# PS3604LF.net
KiCad netlist of a schematic drawn in Altium Designer
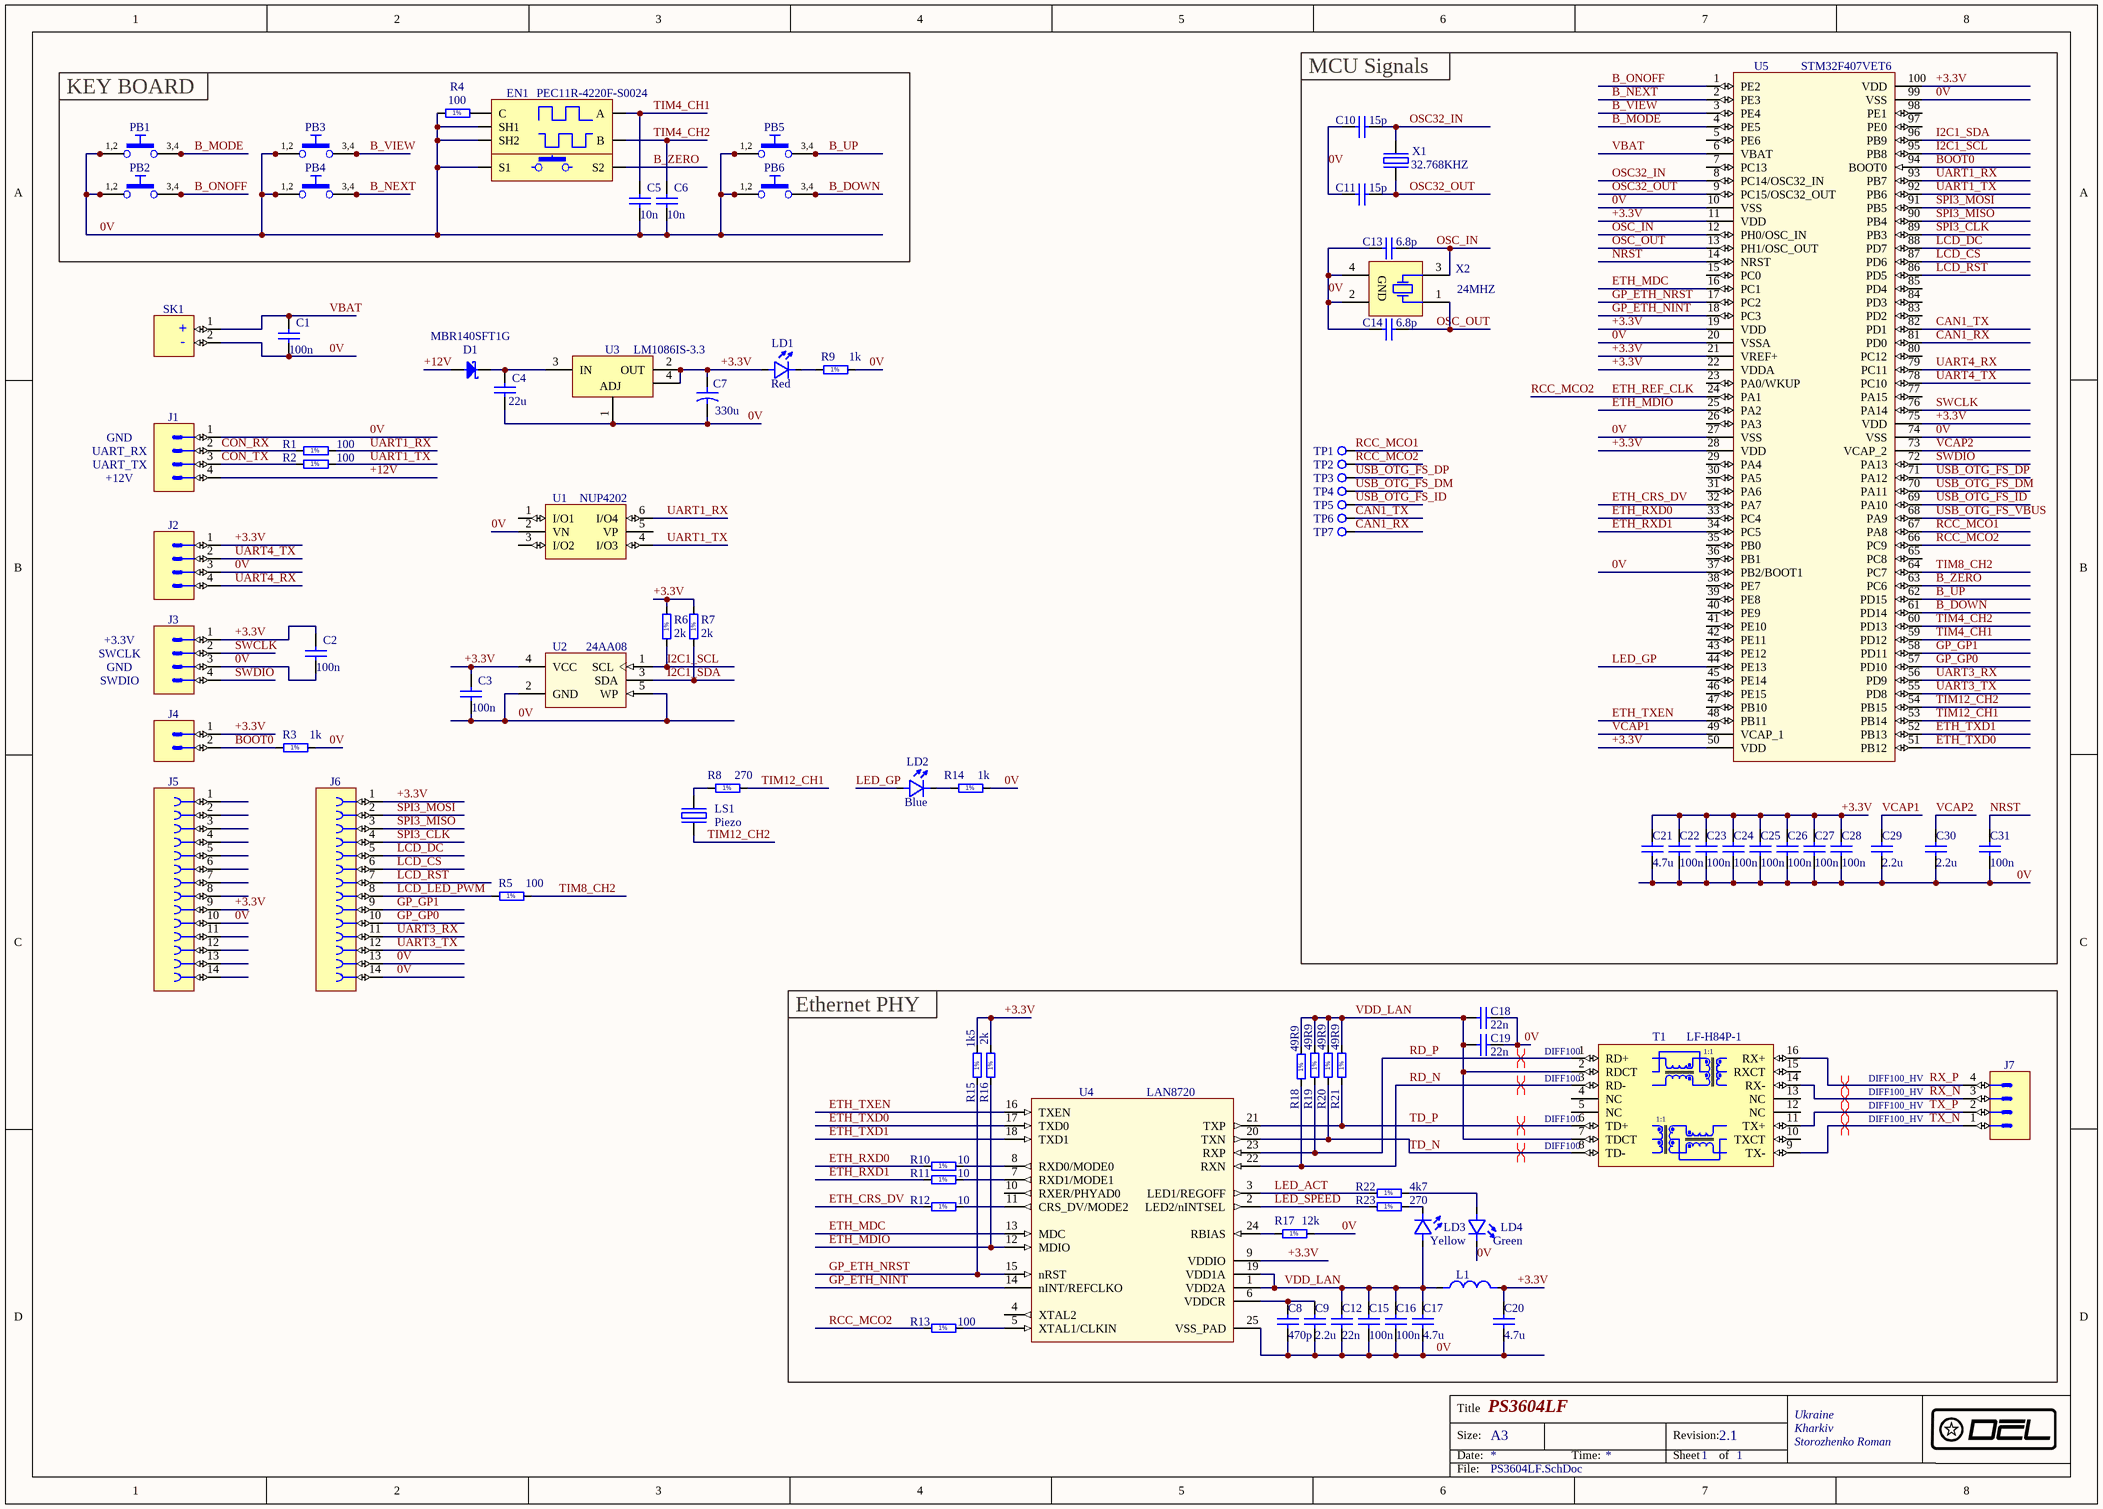
[diagram p0: PS3604LF.SchDoc]

(export (version "E")
  (design (tool "Eeschema 10.0.6"))
  (components
    (comp (ref "C1")
      (value "100n")
      (footprint "CAPC1005X55N")
      (description "Non-polarised capacitor")
      (fields
        (field (name "PART NUMBER") "CC0402_100NF_50V_10%_X7R")
        (field (name "VOLTAGE") "50V")
        (field (name "AUTHOR") "DEL")
      )
      (libsource (lib "Capacitors") (part "Capacitor - non polarized"))
    )
    (comp (ref "C2")
      (value "100n")
      (footprint "CAPC1005X55N")
      (description "Non-polarised capacitor")
      (fields
        (field (name "PART NUMBER") "CC0402_100NF_50V_10%_X7R")
        (field (name "VOLTAGE") "50V")
        (field (name "AUTHOR") "DEL")
      )
      (libsource (lib "Capacitors") (part "Capacitor - non polarized"))
    )
    (comp (ref "C3")
      (value "100n")
      (footprint "CAPC1005X55N")
      (description "Non-polarised capacitor")
      (fields
        (field (name "PART NUMBER") "CC0402_100NF_50V_10%_X7R")
        (field (name "VOLTAGE") "50V")
        (field (name "AUTHOR") "DEL")
      )
      (libsource (lib "Capacitors") (part "Capacitor - non polarized"))
    )
    (comp (ref "C4")
      (value "22u")
      (footprint "CAPC3216X100N")
      (description "Non-polarised capacitor")
      (fields
        (field (name "PART NUMBER") "CC1206_22UF_16V_20%_X5R")
        (field (name "VOLTAGE") "16V")
        (field (name "AUTHOR") "D_EL")
      )
      (libsource (lib "Capacitors") (part "Capacitor - non polarized"))
    )
    (comp (ref "C5")
      (value "10n")
      (footprint "CAPC1005X55N")
      (description "Non-polarised capacitor")
      (fields
        (field (name "PART NUMBER") "CC0402_10NF_50V_10%_X7R")
        (field (name "VOLTAGE") "50V")
        (field (name "AUTHOR") "DEL")
      )
      (libsource (lib "Capacitors") (part "Capacitor - non polarized"))
    )
    (comp (ref "C6")
      (value "10n")
      (footprint "CAPC1005X55N")
      (description "Non-polarised capacitor")
      (fields
        (field (name "PART NUMBER") "CC0402_10NF_50V_10%_X7R")
        (field (name "VOLTAGE") "50V")
        (field (name "AUTHOR") "DEL")
      )
      (libsource (lib "Capacitors") (part "Capacitor - non polarized"))
    )
    (comp (ref "C7")
      (value "330u")
      (footprint "CAPMP7343X310N")
      (description "Polarised capacitor")
      (fields
        (field (name "PART NUMBER") "CTE7343-31_330UF_6.3V_20%_LESR0025_KEMET_T520")
        (field (name "VOLTAGE") "6.3V")
        (field (name "AUTHOR") "CERN DEM JLC")
      )
      (libsource (lib "Capacitors") (part "Capacitor - polarized"))
    )
    (comp (ref "C8")
      (value "470p")
      (footprint "CAPC1005X55N")
      (description "Non-polarised capacitor")
      (fields
        (field (name "PART NUMBER") "CC0402_470PF_50V_10%_X7R")
        (field (name "VOLTAGE") "50V")
        (field (name "AUTHOR") "CERN DEM JLC")
      )
      (libsource (lib "Capacitors") (part "Capacitor - non polarized"))
    )
    (comp (ref "C9")
      (value "2.2u")
      (footprint "CAPC1005X55N")
      (description "Non-polarised capacitor")
      (fields
        (field (name "PART NUMBER") "CC0402_2.2UF_6.3V_20%_X5R")
        (field (name "VOLTAGE") "6.3V")
        (field (name "AUTHOR") "ELMAN")
      )
      (libsource (lib "Capacitors") (part "Capacitor - non polarized"))
    )
    (comp (ref "C10")
      (value "15p")
      (footprint "CAPC1005X55N")
      (description "Non-polarised capacitor")
      (fields
        (field (name "PART NUMBER") "CC0402_15PF_50V_5%_NP0")
        (field (name "VOLTAGE") "50V")
        (field (name "AUTHOR") "CERN DEM JLC")
      )
      (libsource (lib "Capacitors") (part "Capacitor - non polarized"))
    )
    (comp (ref "C11")
      (value "15p")
      (footprint "CAPC1005X55N")
      (description "Non-polarised capacitor")
      (fields
        (field (name "PART NUMBER") "CC0402_15PF_50V_5%_NP0")
        (field (name "VOLTAGE") "50V")
        (field (name "AUTHOR") "CERN DEM JLC")
      )
      (libsource (lib "Capacitors") (part "Capacitor - non polarized"))
    )
    (comp (ref "C12")
      (value "22n")
      (footprint "CAPC1005X55N")
      (description "Non-polarised capacitor")
      (fields
        (field (name "PART NUMBER") "CC0402_22NF_16V_10%_X7R")
        (field (name "VOLTAGE") "16V")
        (field (name "AUTHOR") "CERN DEM JLC")
      )
      (libsource (lib "Capacitors") (part "Capacitor - non polarized"))
    )
    (comp (ref "C13")
      (value "6.8p")
      (footprint "CAPC1005X55N")
      (description "Non-polarised capacitor")
      (fields
        (field (name "PART NUMBER") "CC0402_6.8PF_50V_0.5PF_NP0")
        (field (name "VOLTAGE") "50V")
        (field (name "AUTHOR") "CERN DEM JLC")
      )
      (libsource (lib "Capacitors") (part "Capacitor - non polarized"))
    )
    (comp (ref "C14")
      (value "6.8p")
      (footprint "CAPC1005X55N")
      (description "Non-polarised capacitor")
      (fields
        (field (name "PART NUMBER") "CC0402_6.8PF_50V_0.5PF_NP0")
        (field (name "VOLTAGE") "50V")
        (field (name "AUTHOR") "CERN DEM JLC")
      )
      (libsource (lib "Capacitors") (part "Capacitor - non polarized"))
    )
    (comp (ref "C15")
      (value "100n")
      (footprint "CAPC1005X55N")
      (description "Non-polarised capacitor")
      (fields
        (field (name "PART NUMBER") "CC0402_100NF_50V_10%_X7R")
        (field (name "VOLTAGE") "50V")
        (field (name "AUTHOR") "DEL")
      )
      (libsource (lib "Capacitors") (part "Capacitor - non polarized"))
    )
    (comp (ref "C16")
      (value "100n")
      (footprint "CAPC1005X55N")
      (description "Non-polarised capacitor")
      (fields
        (field (name "PART NUMBER") "CC0402_100NF_50V_10%_X7R")
        (field (name "VOLTAGE") "50V")
        (field (name "AUTHOR") "DEL")
      )
      (libsource (lib "Capacitors") (part "Capacitor - non polarized"))
    )
    (comp (ref "C17")
      (value "4.7u")
      (footprint "CAPC1608X87N")
      (description "Non-polarised capacitor")
      (fields
        (field (name "PART NUMBER") "CC0603_4.7UF_10V_10%_X5R")
        (field (name "VOLTAGE") "10V")
        (field (name "AUTHOR") "ELMAN")
      )
      (libsource (lib "Capacitors") (part "Capacitor - non polarized"))
    )
    (comp (ref "C18")
      (value "22n")
      (footprint "CAPC1005X55N")
      (description "Non-polarised capacitor")
      (fields
        (field (name "PART NUMBER") "CC0402_22NF_16V_10%_X7R")
        (field (name "VOLTAGE") "16V")
        (field (name "AUTHOR") "CERN DEM JLC")
      )
      (libsource (lib "Capacitors") (part "Capacitor - non polarized"))
    )
    (comp (ref "C19")
      (value "22n")
      (footprint "CAPC1005X55N")
      (description "Non-polarised capacitor")
      (fields
        (field (name "PART NUMBER") "CC0402_22NF_16V_10%_X7R")
        (field (name "VOLTAGE") "16V")
        (field (name "AUTHOR") "CERN DEM JLC")
      )
      (libsource (lib "Capacitors") (part "Capacitor - non polarized"))
    )
    (comp (ref "C20")
      (value "4.7u")
      (footprint "CAPC1608X87N")
      (description "Non-polarised capacitor")
      (fields
        (field (name "PART NUMBER") "CC0603_4.7UF_10V_10%_X5R")
        (field (name "VOLTAGE") "10V")
        (field (name "AUTHOR") "ELMAN")
      )
      (libsource (lib "Capacitors") (part "Capacitor - non polarized"))
    )
    (comp (ref "C21")
      (value "4.7u")
      (footprint "CAPC1608X87N")
      (description "Non-polarised capacitor")
      (fields
        (field (name "PART NUMBER") "CC0603_4.7UF_10V_10%_X5R")
        (field (name "VOLTAGE") "10V")
        (field (name "AUTHOR") "ELMAN")
      )
      (libsource (lib "Capacitors") (part "Capacitor - non polarized"))
    )
    (comp (ref "C22")
      (value "100n")
      (footprint "CAPC1005X55N")
      (description "Non-polarised capacitor")
      (fields
        (field (name "PART NUMBER") "CC0402_100NF_50V_10%_X7R")
        (field (name "VOLTAGE") "50V")
        (field (name "AUTHOR") "DEL")
      )
      (libsource (lib "Capacitors") (part "Capacitor - non polarized"))
    )
    (comp (ref "C23")
      (value "100n")
      (footprint "CAPC1005X55N")
      (description "Non-polarised capacitor")
      (fields
        (field (name "PART NUMBER") "CC0402_100NF_50V_10%_X7R")
        (field (name "VOLTAGE") "50V")
        (field (name "AUTHOR") "DEL")
      )
      (libsource (lib "Capacitors") (part "Capacitor - non polarized"))
    )
    (comp (ref "C24")
      (value "100n")
      (footprint "CAPC1005X55N")
      (description "Non-polarised capacitor")
      (fields
        (field (name "PART NUMBER") "CC0402_100NF_50V_10%_X7R")
        (field (name "VOLTAGE") "50V")
        (field (name "AUTHOR") "DEL")
      )
      (libsource (lib "Capacitors") (part "Capacitor - non polarized"))
    )
    (comp (ref "C25")
      (value "100n")
      (footprint "CAPC1005X55N")
      (description "Non-polarised capacitor")
      (fields
        (field (name "PART NUMBER") "CC0402_100NF_50V_10%_X7R")
        (field (name "VOLTAGE") "50V")
        (field (name "AUTHOR") "DEL")
      )
      (libsource (lib "Capacitors") (part "Capacitor - non polarized"))
    )
    (comp (ref "C26")
      (value "100n")
      (footprint "CAPC1005X55N")
      (description "Non-polarised capacitor")
      (fields
        (field (name "PART NUMBER") "CC0402_100NF_50V_10%_X7R")
        (field (name "VOLTAGE") "50V")
        (field (name "AUTHOR") "DEL")
      )
      (libsource (lib "Capacitors") (part "Capacitor - non polarized"))
    )
    (comp (ref "C27")
      (value "100n")
      (footprint "CAPC1005X55N")
      (description "Non-polarised capacitor")
      (fields
        (field (name "PART NUMBER") "CC0402_100NF_50V_10%_X7R")
        (field (name "VOLTAGE") "50V")
        (field (name "AUTHOR") "DEL")
      )
      (libsource (lib "Capacitors") (part "Capacitor - non polarized"))
    )
    (comp (ref "C28")
      (value "100n")
      (footprint "CAPC1005X55N")
      (description "Non-polarised capacitor")
      (fields
        (field (name "PART NUMBER") "CC0402_100NF_50V_10%_X7R")
        (field (name "VOLTAGE") "50V")
        (field (name "AUTHOR") "DEL")
      )
      (libsource (lib "Capacitors") (part "Capacitor - non polarized"))
    )
    (comp (ref "C29")
      (value "2.2u")
      (footprint "CAPC1005X55N")
      (description "Non-polarised capacitor")
      (fields
        (field (name "PART NUMBER") "CC0402_2.2UF_6.3V_20%_X5R")
        (field (name "VOLTAGE") "6.3V")
        (field (name "AUTHOR") "ELMAN")
      )
      (libsource (lib "Capacitors") (part "Capacitor - non polarized"))
    )
    (comp (ref "C30")
      (value "2.2u")
      (footprint "CAPC1005X55N")
      (description "Non-polarised capacitor")
      (fields
        (field (name "PART NUMBER") "CC0402_2.2UF_6.3V_20%_X5R")
        (field (name "VOLTAGE") "6.3V")
        (field (name "AUTHOR") "ELMAN")
      )
      (libsource (lib "Capacitors") (part "Capacitor - non polarized"))
    )
    (comp (ref "C31")
      (value "100n")
      (footprint "CAPC1005X55N")
      (description "Non-polarised capacitor")
      (fields
        (field (name "PART NUMBER") "CC0402_100NF_50V_10%_X7R")
        (field (name "VOLTAGE") "50V")
        (field (name "AUTHOR") "DEL")
      )
      (libsource (lib "Capacitors") (part "Capacitor - non polarized"))
    )
    (comp (ref "D1")
      (value "MBR140SFT1G")
      (footprint "SOD-123FL")
      (description "Schottky Diode")
      (fields
        (field (name "VOLTAGE") "40V")
        (field (name "POWER") "1A")
        (field (name "AUTHOR") "CERN DEM JLC")
      )
      (libsource (lib "ICs And Semiconductors") (part "Diode Schottky"))
    )
    (comp (ref "EN1")
      (value "PEC11R-4220F-S0024")
      (footprint "EN_BOURNS_PEC11R-4x20F-Sxxxx")
      (description "Encoder incremental with push momentary switch")
      (fields
        (field (name "PART NUMBER") "EN_BOUNCE_PEC11R-4220F-S0024")
        (field (name "MANUFACTURER") "BOURNS")
        (field (name "AUTHOR") "DEL")
      )
      (libsource (lib "Eletro-mechanical") (part "EN Incremental"))
    )
    (comp (ref "J1")
      (value "SPOX")
      (footprint "MOLEX_22-03-5045")
      (description "Connector 4 Male")
      (fields
        (field (name "PART NUMBER") "MOLEX_22-03-5045")
        (field (name "MANUFACTURER") "MOLEX")
        (field (name "AUTHOR") "DEL")
      )
      (libsource (lib "Connectors") (part "Connector 4 Male"))
    )
    (comp (ref "J2")
      (value "Header 4")
      (footprint "3M_2304-6111-TG")
      (description "Connector 4 Male")
      (fields
        (field (name "PART NUMBER") "3M_2304-6111-TG")
        (field (name "MANUFACTURER") "3M")
        (field (name "AUTHOR") "DEL")
      )
      (libsource (lib "Connectors") (part "Connector 4 Male"))
    )
    (comp (ref "J3")
      (value "Header 4")
      (footprint "3M_2304-6111-TG")
      (description "Connector 4 Male")
      (fields
        (field (name "PART NUMBER") "3M_2304-6111-TG")
        (field (name "MANUFACTURER") "3M")
        (field (name "AUTHOR") "DEL")
      )
      (libsource (lib "Connectors") (part "Connector 4 Male"))
    )
    (comp (ref "J4")
      (value "Header 2")
      (footprint "3M_2302-6111-TG")
      (description "Connector 2 Male")
      (fields
        (field (name "PART NUMBER") "3M_2302-6111-TG")
        (field (name "MANUFACTURER") "3M")
        (field (name "AUTHOR") "DEL")
      )
      (libsource (lib "Connectors") (part "Connector 2 Male"))
    )
    (comp (ref "J5")
      (value "Socket 14")
      (footprint "3M_955114-6102-AR")
      (description "Connector 14 Female")
      (fields
        (field (name "PART NUMBER") "3M_955114-6102-AR")
        (field (name "MANUFACTURER") "3M")
        (field (name "AUTHOR") "DEL")
      )
      (libsource (lib "Connectors") (part "Connector 14 Female"))
    )
    (comp (ref "J6")
      (value "Socket 14")
      (footprint "3M_955114-6102-AR")
      (description "Connector 14 Female")
      (fields
        (field (name "PART NUMBER") "3M_955114-6102-AR")
        (field (name "MANUFACTURER") "3M")
        (field (name "AUTHOR") "DEL")
      )
      (libsource (lib "Connectors") (part "Connector 14 Female"))
    )
    (comp (ref "J7")
      (value "SPOX")
      (footprint "MOLEX_22-03-5045")
      (description "Connector 4 Male")
      (fields
        (field (name "PART NUMBER") "MOLEX_22-03-5045")
        (field (name "MANUFACTURER") "MOLEX")
        (field (name "AUTHOR") "DEL")
      )
      (libsource (lib "") (part "Connector 4 Male_1"))
    )
    (comp (ref "L1")
      (value "2.2uH")
      (footprint "INDC2520X100N")
      (description "Inductor")
      (fields
        (field (name "PART NUMBER") "IND1008_2.2UH_20%_TDK_MLP2520S2R2MT0S1")
        (field (name "POWER") "1.2A")
        (field (name "AUTHOR") "ELMAN")
      )
      (libsource (lib "Inductors & Transformers") (part "Inductor"))
    )
    (comp (ref "LD1")
      (value "Red")
      (footprint "LEDC1608X80N_RED")
      (description "LED 1C 2A")
      (fields
        (field (name "PART NUMBER") "LED_OF-SMD1608R")
        (field (name "MANUFACTURER") "OPTOFLASH")
        (field (name "AUTHOR") "ELMAN")
      )
      (libsource (lib "ICs And Semiconductors") (part "LED 1C 2A"))
    )
    (comp (ref "LD2")
      (value "Blue")
      (footprint "LEDC1608X80N_BLUE")
      (description "LED 1C 2A")
      (fields
        (field (name "PART NUMBER") "LED_OF-SMD1608B")
        (field (name "MANUFACTURER") "OPTOFLASH")
        (field (name "AUTHOR") "DEL")
      )
      (libsource (lib "ICs And Semiconductors") (part "LED 1C 2A"))
    )
    (comp (ref "LD3")
      (value "Yellow")
      (footprint "LEDC1608X80N_YELLOW")
      (description "LED 1C 2A")
      (fields
        (field (name "PART NUMBER") "LED_OF-SMD1608Y")
        (field (name "MANUFACTURER") "OPTOFLASH")
        (field (name "AUTHOR") "DEL")
      )
      (libsource (lib "ICs And Semiconductors") (part "LED 1C 2A"))
    )
    (comp (ref "LD4")
      (value "Green")
      (footprint "LEDC1608X80N_GREEN")
      (description "LED 1C 2A")
      (fields
        (field (name "PART NUMBER") "LED_OF-SMD1608G")
        (field (name "MANUFACTURER") "OPTOFLASH")
        (field (name "AUTHOR") "ELMAN")
      )
      (libsource (lib "ICs And Semiconductors") (part "LED 1C 2A"))
    )
    (comp (ref "LS1")
      (value "Piezo")
      (footprint "HPS13C")
      (description "Piezo Sounder")
      (fields
        (field (name "PART NUMBER") "HPS13C")
        (field (name "MANUFACTURER") "JL WORLD")
        (field (name "AUTHOR") "DEL")
      )
      (libsource (lib "Eletro-mechanical") (part "Piezo Sounder"))
    )
    (comp (ref "PB1")
      (value "Push Button")
      (footprint "PB_E-SWITCH_TL1105HF100Q")
      (description "Push-Button Switch SPDT")
      (fields
        (field (name "PART NUMBER") "PB_E-SWITCH_TL1105HF100Q")
        (field (name "MANUFACTURER") "E-SWITCH")
        (field (name "AUTHOR") "DEL")
      )
      (libsource (lib "Eletro-mechanical") (part "PB SPST 12NO-34NO"))
    )
    (comp (ref "PB2")
      (value "Push Button")
      (footprint "PB_E-SWITCH_TL1105HF100Q")
      (description "Push-Button Switch SPDT")
      (fields
        (field (name "PART NUMBER") "PB_E-SWITCH_TL1105HF100Q")
        (field (name "MANUFACTURER") "E-SWITCH")
        (field (name "AUTHOR") "DEL")
      )
      (libsource (lib "Eletro-mechanical") (part "PB SPST 12NO-34NO"))
    )
    (comp (ref "PB3")
      (value "Push Button")
      (footprint "PB_E-SWITCH_TL1105HF100Q")
      (description "Push-Button Switch SPDT")
      (fields
        (field (name "PART NUMBER") "PB_E-SWITCH_TL1105HF100Q")
        (field (name "MANUFACTURER") "E-SWITCH")
        (field (name "AUTHOR") "DEL")
      )
      (libsource (lib "Eletro-mechanical") (part "PB SPST 12NO-34NO"))
    )
    (comp (ref "PB4")
      (value "Push Button")
      (footprint "PB_E-SWITCH_TL1105HF100Q")
      (description "Push-Button Switch SPDT")
      (fields
        (field (name "PART NUMBER") "PB_E-SWITCH_TL1105HF100Q")
        (field (name "MANUFACTURER") "E-SWITCH")
        (field (name "AUTHOR") "DEL")
      )
      (libsource (lib "Eletro-mechanical") (part "PB SPST 12NO-34NO"))
    )
    (comp (ref "PB5")
      (value "Push Button")
      (footprint "PB_E-SWITCH_TL1105HF100Q")
      (description "Push-Button Switch SPDT")
      (fields
        (field (name "PART NUMBER") "PB_E-SWITCH_TL1105HF100Q")
        (field (name "MANUFACTURER") "E-SWITCH")
        (field (name "AUTHOR") "DEL")
      )
      (libsource (lib "Eletro-mechanical") (part "PB SPST 12NO-34NO"))
    )
    (comp (ref "PB6")
      (value "Push Button")
      (footprint "PB_E-SWITCH_TL1105HF100Q")
      (description "Push-Button Switch SPDT")
      (fields
        (field (name "PART NUMBER") "PB_E-SWITCH_TL1105HF100Q")
        (field (name "MANUFACTURER") "E-SWITCH")
        (field (name "AUTHOR") "DEL")
      )
      (libsource (lib "Eletro-mechanical") (part "PB SPST 12NO-34NO"))
    )
    (comp (ref "R1")
      (value "100")
      (footprint "RESC1005X40N")
      (description "Resistor - 1%")
      (fields
        (field (name "PART NUMBER") "R0402_100R_1%_0.0625W_100PPM")
        (field (name "POWER") "0.0625W")
        (field (name "AUTHOR") "CERN DEM JLC")
      )
      (libsource (lib "Resistors") (part "Resistor - 1%"))
    )
    (comp (ref "R2")
      (value "100")
      (footprint "RESC1005X40N")
      (description "Resistor - 1%")
      (fields
        (field (name "PART NUMBER") "R0402_100R_1%_0.0625W_100PPM")
        (field (name "POWER") "0.0625W")
        (field (name "AUTHOR") "CERN DEM JLC")
      )
      (libsource (lib "Resistors") (part "Resistor - 1%"))
    )
    (comp (ref "R3")
      (value "1k")
      (footprint "RESC1005X40N")
      (description "Resistor - 1%")
      (fields
        (field (name "PART NUMBER") "R0402_1K_1%_0.0625W_100PPM")
        (field (name "POWER") "0.0625W")
        (field (name "AUTHOR") "CERN DEM JLC")
      )
      (libsource (lib "Resistors") (part "Resistor - 1%"))
    )
    (comp (ref "R4")
      (value "100")
      (footprint "RESC1005X40N")
      (description "Resistor - 1%")
      (fields
        (field (name "PART NUMBER") "R0402_100R_1%_0.0625W_100PPM")
        (field (name "POWER") "0.0625W")
        (field (name "AUTHOR") "CERN DEM JLC")
      )
      (libsource (lib "Resistors") (part "Resistor - 1%"))
    )
    (comp (ref "R5")
      (value "100")
      (footprint "RESC1005X40N")
      (description "Resistor - 1%")
      (fields
        (field (name "PART NUMBER") "R0402_100R_1%_0.0625W_100PPM")
        (field (name "POWER") "0.0625W")
        (field (name "AUTHOR") "CERN DEM JLC")
      )
      (libsource (lib "Resistors") (part "Resistor - 1%"))
    )
    (comp (ref "R6")
      (value "2k")
      (footprint "RESC1005X40N")
      (description "Resistor - 1%")
      (fields
        (field (name "PART NUMBER") "R0402_2K_1%_0.0625W_100PPM")
        (field (name "POWER") "0.0625W")
        (field (name "AUTHOR") "CERN DEM JLC")
      )
      (libsource (lib "Resistors") (part "Resistor - 1%"))
    )
    (comp (ref "R7")
      (value "2k")
      (footprint "RESC1005X40N")
      (description "Resistor - 1%")
      (fields
        (field (name "PART NUMBER") "R0402_2K_1%_0.0625W_100PPM")
        (field (name "POWER") "0.0625W")
        (field (name "AUTHOR") "CERN DEM JLC")
      )
      (libsource (lib "Resistors") (part "Resistor - 1%"))
    )
    (comp (ref "R8")
      (value "270")
      (footprint "RESC1005X40N")
      (description "Resistor - 1%")
      (fields
        (field (name "PART NUMBER") "R0402_270R_1%_0.0625W_100PPM")
        (field (name "POWER") "0.0625W")
        (field (name "AUTHOR") "CERN DEM JLC")
      )
      (libsource (lib "Resistors") (part "Resistor - 1%"))
    )
    (comp (ref "R9")
      (value "1k")
      (footprint "RESC1005X40N")
      (description "Resistor - 1%")
      (fields
        (field (name "PART NUMBER") "R0402_1K_1%_0.0625W_100PPM")
        (field (name "POWER") "0.0625W")
        (field (name "AUTHOR") "CERN DEM JLC")
      )
      (libsource (lib "Resistors") (part "Resistor - 1%"))
    )
    (comp (ref "R10")
      (value "10")
      (footprint "RESC1005X40N")
      (description "Resistor - 1%")
      (fields
        (field (name "PART NUMBER") "R0402_10R_1%_0.0625W_200PPM")
        (field (name "POWER") "0.0625W")
        (field (name "AUTHOR") "CERN DEM JLC")
      )
      (libsource (lib "Resistors") (part "Resistor - 1%"))
    )
    (comp (ref "R11")
      (value "10")
      (footprint "RESC1005X40N")
      (description "Resistor - 1%")
      (fields
        (field (name "PART NUMBER") "R0402_10R_1%_0.0625W_200PPM")
        (field (name "POWER") "0.0625W")
        (field (name "AUTHOR") "CERN DEM JLC")
      )
      (libsource (lib "Resistors") (part "Resistor - 1%"))
    )
    (comp (ref "R12")
      (value "10")
      (footprint "RESC1005X40N")
      (description "Resistor - 1%")
      (fields
        (field (name "PART NUMBER") "R0402_10R_1%_0.0625W_200PPM")
        (field (name "POWER") "0.0625W")
        (field (name "AUTHOR") "CERN DEM JLC")
      )
      (libsource (lib "Resistors") (part "Resistor - 1%"))
    )
    (comp (ref "R13")
      (value "100")
      (footprint "RESC1005X40N")
      (description "Resistor - 1%")
      (fields
        (field (name "PART NUMBER") "R0402_100R_1%_0.0625W_100PPM")
        (field (name "POWER") "0.0625W")
        (field (name "AUTHOR") "CERN DEM JLC")
      )
      (libsource (lib "Resistors") (part "Resistor - 1%"))
    )
    (comp (ref "R14")
      (value "1k")
      (footprint "RESC1005X40N")
      (description "Resistor - 1%")
      (fields
        (field (name "PART NUMBER") "R0402_1K_1%_0.0625W_100PPM")
        (field (name "POWER") "0.0625W")
        (field (name "AUTHOR") "CERN DEM JLC")
      )
      (libsource (lib "Resistors") (part "Resistor - 1%"))
    )
    (comp (ref "R15")
      (value "1k5")
      (footprint "RESC1005X40N")
      (description "Resistor - 1%")
      (fields
        (field (name "PART NUMBER") "R0402_1K5_1%_0.0625W_100PPM")
        (field (name "POWER") "0.0625W")
        (field (name "AUTHOR") "CERN DEM JLC")
      )
      (libsource (lib "Resistors") (part "Resistor - 1%"))
    )
    (comp (ref "R16")
      (value "2k")
      (footprint "RESC1005X40N")
      (description "Resistor - 1%")
      (fields
        (field (name "PART NUMBER") "R0402_2K_1%_0.0625W_100PPM")
        (field (name "POWER") "0.0625W")
        (field (name "AUTHOR") "CERN DEM JLC")
      )
      (libsource (lib "Resistors") (part "Resistor - 1%"))
    )
    (comp (ref "R17")
      (value "12k")
      (footprint "RESC1005X40N")
      (description "Resistor - 1%")
      (fields
        (field (name "PART NUMBER") "R0402_12K_1%_0.0625W_100PPM")
        (field (name "POWER") "0.0625W")
        (field (name "AUTHOR") "CERN DEM JLC")
      )
      (libsource (lib "Resistors") (part "Resistor - 1%"))
    )
    (comp (ref "R18")
      (value "49R9")
      (footprint "RESC1005X40N")
      (description "Resistor - 1%")
      (fields
        (field (name "PART NUMBER") "R0402_49R9_1%_0.0625W_100PPM")
        (field (name "POWER") "0.0625W")
        (field (name "AUTHOR") "ELMAN")
      )
      (libsource (lib "Resistors") (part "Resistor - 1%"))
    )
    (comp (ref "R19")
      (value "49R9")
      (footprint "RESC1005X40N")
      (description "Resistor - 1%")
      (fields
        (field (name "PART NUMBER") "R0402_49R9_1%_0.0625W_100PPM")
        (field (name "POWER") "0.0625W")
        (field (name "AUTHOR") "ELMAN")
      )
      (libsource (lib "Resistors") (part "Resistor - 1%"))
    )
    (comp (ref "R20")
      (value "49R9")
      (footprint "RESC1005X40N")
      (description "Resistor - 1%")
      (fields
        (field (name "PART NUMBER") "R0402_49R9_1%_0.0625W_100PPM")
        (field (name "POWER") "0.0625W")
        (field (name "AUTHOR") "ELMAN")
      )
      (libsource (lib "Resistors") (part "Resistor - 1%"))
    )
    (comp (ref "R21")
      (value "49R9")
      (footprint "RESC1005X40N")
      (description "Resistor - 1%")
      (fields
        (field (name "PART NUMBER") "R0402_49R9_1%_0.0625W_100PPM")
        (field (name "POWER") "0.0625W")
        (field (name "AUTHOR") "ELMAN")
      )
      (libsource (lib "Resistors") (part "Resistor - 1%"))
    )
    (comp (ref "R22")
      (value "4k7")
      (footprint "RESC1005X40N")
      (description "Resistor - 1%")
      (fields
        (field (name "PART NUMBER") "R0402_4K7_1%_0.0625W_100PPM")
        (field (name "POWER") "0.0625W")
        (field (name "AUTHOR") "CERN DEM JLC")
      )
      (libsource (lib "Resistors") (part "Resistor - 1%"))
    )
    (comp (ref "R23")
      (value "270")
      (footprint "RESC1005X40N")
      (description "Resistor - 1%")
      (fields
        (field (name "PART NUMBER") "R0402_270R_1%_0.0625W_100PPM")
        (field (name "POWER") "0.0625W")
        (field (name "AUTHOR") "CERN DEM JLC")
      )
      (libsource (lib "Resistors") (part "Resistor - 1%"))
    )
    (comp (ref "SK1")
      (value "BH500")
      (footprint "EEMB_BH500")
      (description "Battery holder")
      (fields
        (field (name "PART NUMBER") "EEMB_BH500")
        (field (name "MANUFACTURER") "EEMB")
        (field (name "AUTHOR") "DEL")
      )
      (libsource (lib "Eletro-mechanical") (part "BAT_HOLDER"))
    )
    (comp (ref "T1")
      (value "LF-H84P-1")
      (footprint "XFMR_LF-H84P")
      (description "Signal Transformers 10/100 Base-T XFMR 1 Port LAN")
      (fields
        (field (name "PART NUMBER") "PE-68678")
        (field (name "MANUFACTURER") "LANKom")
        (field (name "AUTHOR") "DEL")
      )
      (libsource (lib "Inductors & Transformers") (part "XFMR_10/100 Base-T"))
    )
    (comp (ref "TP1")
      (value "Test Point")
      (footprint "TP_SMD_800")
      (fields (field (name "PART NUMBER") "TP_SMD_0.8MM") (field (name "AUTHOR") "DEL"))
      (libsource (lib "Eletro-mechanical") (part "Test Point"))
    )
    (comp (ref "TP2")
      (value "Test Point")
      (footprint "TP_SMD_800")
      (fields (field (name "PART NUMBER") "TP_SMD_0.8MM") (field (name "AUTHOR") "DEL"))
      (libsource (lib "Eletro-mechanical") (part "Test Point"))
    )
    (comp (ref "TP3")
      (value "Test Point")
      (footprint "TP_SMD_800")
      (fields (field (name "PART NUMBER") "TP_SMD_0.8MM") (field (name "AUTHOR") "DEL"))
      (libsource (lib "Eletro-mechanical") (part "Test Point"))
    )
    (comp (ref "TP4")
      (value "Test Point")
      (footprint "TP_SMD_800")
      (fields (field (name "PART NUMBER") "TP_SMD_0.8MM") (field (name "AUTHOR") "DEL"))
      (libsource (lib "Eletro-mechanical") (part "Test Point"))
    )
    (comp (ref "TP5")
      (value "Test Point")
      (footprint "TP_SMD_800")
      (fields (field (name "PART NUMBER") "TP_SMD_0.8MM") (field (name "AUTHOR") "DEL"))
      (libsource (lib "Eletro-mechanical") (part "Test Point"))
    )
    (comp (ref "TP6")
      (value "Test Point")
      (footprint "TP_SMD_800")
      (fields (field (name "PART NUMBER") "TP_SMD_0.8MM") (field (name "AUTHOR") "DEL"))
      (libsource (lib "Eletro-mechanical") (part "Test Point"))
    )
    (comp (ref "TP7")
      (value "Test Point")
      (footprint "TP_SMD_800")
      (fields (field (name "PART NUMBER") "TP_SMD_0.8MM") (field (name "AUTHOR") "DEL"))
      (libsource (lib "Eletro-mechanical") (part "Test Point"))
    )
    (comp (ref "U1")
      (value "NUP4202")
      (footprint "SOT65P220X110-6N")
      (description "ESD Protection Diode, Low  Clamping Voltage")
      (fields
        (field (name "PART NUMBER") "NUP4202W1")
        (field (name "MANUFACTURER") "ON SEMICONDUCTOR")
        (field (name "AUTHOR") "DEL")
      )
      (libsource (lib "ICs And Semiconductors") (part "NUP4202"))
    )
    (comp (ref "U2")
      (value "24AA08")
      (footprint "SOT95P280X145-5N")
      (description "I2C™ Serial EEPROM SOT23-5 Package")
      (fields
        (field (name "PART NUMBER") "24AA08T-I/OT")
        (field (name "MANUFACTURER") "MICROCHIP")
        (field (name "AUTHOR") "DEL")
      )
      (libsource (lib "ICs And Semiconductors") (part "24AAxxT-x/OT"))
    )
    (comp (ref "U3")
      (value "LM1086IS-3.3")
      (footprint "TO254P1435X464-4N-R1041X635")
      (description "3-Terminal Regulator 1=Adj 2=OUT 3=IN 4=OUT")
      (fields (field (name "MANUFACTURER") "TEXAS INSTRUMENTS") (field (name "AUTHOR") "D_EL"))
      (libsource (lib "ICs And Semiconductors") (part "REG3+1 1ADJ-2OUT-3IN+4OUT"))
    )
    (comp (ref "U4")
      (value "LAN8720")
      (footprint "QFN50P400X400X100-25N-S265")
      (fields
        (field (name "PART NUMBER") "LAN8720A-CP-TR")
        (field (name "MANUFACTURER") "Microchip")
        (field (name "AUTHOR") "DEL")
      )
      (libsource (lib "ICs And Semiconductors") (part "LAN8720"))
    )
    (comp (ref "U5")
      (value "STM32F407VET6")
      (footprint "QFP50P1600X1600X160-100N")
      (fields (field (name "MANUFACTURER") "ST Microelectronics") (field (name "AUTHOR") "DEL"))
      (libsource (lib "ICs And Semiconductors") (part "STM32F407VxT"))
    )
    (comp (ref "X1")
      (value "32.768KHZ")
      (footprint "OSCCC150X320X80-2N")
      (description "Quartz Crystal")
      (fields
        (field (name "PART NUMBER") "32.768KHz_KX–327NHT")
        (field (name "MANUFACTURER") "GEYER")
        (field (name "AUTHOR") "D_EL")
      )
      (libsource (lib "Crystals & Oscillators") (part "Quartz Crystal"))
    )
    (comp (ref "X2")
      (value "24MHZ")
      (footprint "OSCCC160X200X65-4N")
      (description "Crystal 4 pins 1=XTAL 2=GND3=XTAL 4=GND")
      (fields
        (field (name "PART NUMBER") "24MHZ_XRCGB24M000F3M00R0")
        (field (name "MANUFACTURER") "MURATA")
        (field (name "AUTHOR") "D_EL")
      )
      (libsource (lib "Crystals & Oscillators") (part "Quartz Crystal 1X 2GND 3X 4GND"))
    )
  )
  (nets
    (net (code "1") (name "/+3.3V") (class "Default")
      (node (ref "C2") (pin "2") (pinfunction "2_2") (pintype "passive"))
      (node (ref "C20") (pin "2") (pinfunction "2_2") (pintype "passive"))
      (node (ref "C21") (pin "2") (pinfunction "2_2") (pintype "passive"))
      (node (ref "C22") (pin "2") (pinfunction "2_2") (pintype "passive"))
      (node (ref "C23") (pin "2") (pinfunction "2_2") (pintype "passive"))
      (node (ref "C24") (pin "2") (pinfunction "2_2") (pintype "passive"))
      (node (ref "C25") (pin "2") (pinfunction "2_2") (pintype "passive"))
      (node (ref "C26") (pin "2") (pinfunction "2_2") (pintype "passive"))
      (node (ref "C27") (pin "2") (pinfunction "2_2") (pintype "passive"))
      (node (ref "C28") (pin "2") (pinfunction "2_2") (pintype "passive"))
      (node (ref "C3") (pin "2") (pinfunction "2_2") (pintype "passive"))
      (node (ref "C7") (pin "1") (pinfunction "1_1") (pintype "passive"))
      (node (ref "J2") (pin "1") (pinfunction "1_1") (pintype "bidirectional"))
      (node (ref "J3") (pin "1") (pinfunction "1_1") (pintype "bidirectional"))
      (node (ref "J4") (pin "1") (pinfunction "1_1") (pintype "bidirectional"))
      (node (ref "J5") (pin "9") (pinfunction "9_9") (pintype "bidirectional"))
      (node (ref "J6") (pin "1") (pinfunction "1_1") (pintype "bidirectional"))
      (node (ref "L1") (pin "2") (pinfunction "2_2") (pintype "passive"))
      (node (ref "LD1") (pin "2") (pinfunction "A_2") (pintype "passive"))
      (node (ref "R15") (pin "2") (pinfunction "2_2") (pintype "passive"))
      (node (ref "R16") (pin "2") (pinfunction "2_2") (pintype "passive"))
      (node (ref "R6") (pin "2") (pinfunction "2_2") (pintype "passive"))
      (node (ref "R7") (pin "2") (pinfunction "2_2") (pintype "passive"))
      (node (ref "U2") (pin "4") (pinfunction "VCC_4") (pintype "power_in"))
      (node (ref "U3") (pin "2") (pinfunction "OUT_2") (pintype "power_in"))
      (node (ref "U3") (pin "4") (pinfunction "OUT_4") (pintype "power_in"))
      (node (ref "U4") (pin "9") (pinfunction "VDDIO_9") (pintype "power_in"))
      (node (ref "U5") (pin "100") (pinfunction "VDD_100") (pintype "power_in"))
      (node (ref "U5") (pin "11") (pinfunction "VDD_11") (pintype "power_in"))
      (node (ref "U5") (pin "19") (pinfunction "VDD_19") (pintype "power_in"))
      (node (ref "U5") (pin "21") (pinfunction "VREF+_21") (pintype "power_in"))
      (node (ref "U5") (pin "22") (pinfunction "VDDA_22") (pintype "power_in"))
      (node (ref "U5") (pin "28") (pinfunction "VDD_28") (pintype "power_in"))
      (node (ref "U5") (pin "50") (pinfunction "VDD_50") (pintype "power_in"))
      (node (ref "U5") (pin "75") (pinfunction "VDD_75") (pintype "power_in"))
    )
    (net (code "2") (name "/+12V") (class "Default")
      (node (ref "D1") (pin "2") (pinfunction "A_2") (pintype "passive"))
      (node (ref "J1") (pin "4") (pinfunction "4_4") (pintype "bidirectional"))
    )
    (net (code "3") (name "/0V") (class "Default")
      (node (ref "C1") (pin "1") (pinfunction "1_1") (pintype "passive"))
      (node (ref "C10") (pin "1") (pinfunction "1_1") (pintype "passive"))
      (node (ref "C11") (pin "1") (pinfunction "1_1") (pintype "passive"))
      (node (ref "C12") (pin "2") (pinfunction "2_2") (pintype "passive"))
      (node (ref "C13") (pin "1") (pinfunction "1_1") (pintype "passive"))
      (node (ref "C14") (pin "1") (pinfunction "1_1") (pintype "passive"))
      (node (ref "C15") (pin "1") (pinfunction "1_1") (pintype "passive"))
      (node (ref "C16") (pin "1") (pinfunction "1_1") (pintype "passive"))
      (node (ref "C17") (pin "1") (pinfunction "1_1") (pintype "passive"))
      (node (ref "C18") (pin "2") (pinfunction "2_2") (pintype "passive"))
      (node (ref "C19") (pin "2") (pinfunction "2_2") (pintype "passive"))
      (node (ref "C2") (pin "1") (pinfunction "1_1") (pintype "passive"))
      (node (ref "C20") (pin "1") (pinfunction "1_1") (pintype "passive"))
      (node (ref "C21") (pin "1") (pinfunction "1_1") (pintype "passive"))
      (node (ref "C22") (pin "1") (pinfunction "1_1") (pintype "passive"))
      (node (ref "C23") (pin "1") (pinfunction "1_1") (pintype "passive"))
      (node (ref "C24") (pin "1") (pinfunction "1_1") (pintype "passive"))
      (node (ref "C25") (pin "1") (pinfunction "1_1") (pintype "passive"))
      (node (ref "C26") (pin "1") (pinfunction "1_1") (pintype "passive"))
      (node (ref "C27") (pin "1") (pinfunction "1_1") (pintype "passive"))
      (node (ref "C28") (pin "1") (pinfunction "1_1") (pintype "passive"))
      (node (ref "C29") (pin "1") (pinfunction "1_1") (pintype "passive"))
      (node (ref "C3") (pin "1") (pinfunction "1_1") (pintype "passive"))
      (node (ref "C30") (pin "1") (pinfunction "1_1") (pintype "passive"))
      (node (ref "C31") (pin "1") (pinfunction "1_1") (pintype "passive"))
      (node (ref "C4") (pin "1") (pinfunction "1_1") (pintype "passive"))
      (node (ref "C5") (pin "1") (pinfunction "1_1") (pintype "passive"))
      (node (ref "C6") (pin "1") (pinfunction "1_1") (pintype "passive"))
      (node (ref "C7") (pin "2") (pinfunction "2_2") (pintype "passive"))
      (node (ref "C8") (pin "1") (pinfunction "1_1") (pintype "passive"))
      (node (ref "C9") (pin "1") (pinfunction "1_1") (pintype "passive"))
      (node (ref "EN1") (pin "S1") (pinfunction "S1_S1") (pintype "passive"))
      (node (ref "EN1") (pin "SH1") (pinfunction "SH1_SH1") (pintype "passive"))
      (node (ref "EN1") (pin "SH2") (pinfunction "SH2_SH2") (pintype "passive"))
      (node (ref "J1") (pin "1") (pinfunction "1_1") (pintype "bidirectional"))
      (node (ref "J2") (pin "3") (pinfunction "3_3") (pintype "bidirectional"))
      (node (ref "J3") (pin "3") (pinfunction "3_3") (pintype "bidirectional"))
      (node (ref "J5") (pin "10") (pinfunction "10_10") (pintype "bidirectional"))
      (node (ref "J6") (pin "13") (pinfunction "13_13") (pintype "bidirectional"))
      (node (ref "J6") (pin "14") (pinfunction "14_14") (pintype "bidirectional"))
      (node (ref "LD4") (pin "1") (pinfunction "C_1") (pintype "passive"))
      (node (ref "PB1") (pin "1") (pinfunction "1_1") (pintype "passive"))
      (node (ref "PB1") (pin "2") (pinfunction "2_2") (pintype "passive"))
      (node (ref "PB2") (pin "1") (pinfunction "1_1") (pintype "passive"))
      (node (ref "PB2") (pin "2") (pinfunction "2_2") (pintype "passive"))
      (node (ref "PB3") (pin "1") (pinfunction "1_1") (pintype "passive"))
      (node (ref "PB3") (pin "2") (pinfunction "2_2") (pintype "passive"))
      (node (ref "PB4") (pin "1") (pinfunction "1_1") (pintype "passive"))
      (node (ref "PB4") (pin "2") (pinfunction "2_2") (pintype "passive"))
      (node (ref "PB5") (pin "1") (pinfunction "1_1") (pintype "passive"))
      (node (ref "PB5") (pin "2") (pinfunction "2_2") (pintype "passive"))
      (node (ref "PB6") (pin "1") (pinfunction "1_1") (pintype "passive"))
      (node (ref "PB6") (pin "2") (pinfunction "2_2") (pintype "passive"))
      (node (ref "R14") (pin "2") (pinfunction "2_2") (pintype "passive"))
      (node (ref "R17") (pin "2") (pinfunction "2_2") (pintype "passive"))
      (node (ref "R3") (pin "2") (pinfunction "2_2") (pintype "passive"))
      (node (ref "R4") (pin "1") (pinfunction "1_1") (pintype "passive"))
      (node (ref "R9") (pin "2") (pinfunction "2_2") (pintype "passive"))
      (node (ref "SK1") (pin "2") (pinfunction "2_2") (pintype "bidirectional"))
      (node (ref "U1") (pin "2") (pinfunction "VN_2") (pintype "power_in"))
      (node (ref "U2") (pin "2") (pinfunction "GND_2") (pintype "power_in"))
      (node (ref "U2") (pin "5") (pinfunction "WP_5") (pintype "input"))
      (node (ref "U3") (pin "1") (pinfunction "ADJ_1") (pintype "power_in"))
      (node (ref "U4") (pin "25") (pinfunction "VSS_PAD_25") (pintype "power_in"))
      (node (ref "U5") (pin "10") (pinfunction "VSS_10") (pintype "power_in"))
      (node (ref "U5") (pin "20") (pinfunction "VSSA_20") (pintype "power_in"))
      (node (ref "U5") (pin "27") (pinfunction "VSS_27") (pintype "power_in"))
      (node (ref "U5") (pin "37") (pinfunction "PB2/BOOT1_37") (pintype "bidirectional"))
      (node (ref "U5") (pin "74") (pinfunction "VSS_74") (pintype "power_in"))
      (node (ref "U5") (pin "99") (pinfunction "VSS_99") (pintype "power_in"))
      (node (ref "X2") (pin "2") (pinfunction "GND_2") (pintype "power_in"))
      (node (ref "X2") (pin "4") (pinfunction "GND_4") (pintype "power_in"))
    )
    (net (code "4") (name "/BOOT0") (class "Default")
      (node (ref "J4") (pin "2") (pinfunction "2_2") (pintype "bidirectional"))
      (node (ref "R3") (pin "1") (pinfunction "1_1") (pintype "passive"))
      (node (ref "U5") (pin "94") (pinfunction "BOOT0_94") (pintype "input"))
    )
    (net (code "5") (name "/B_DOWN") (class "Default")
      (node (ref "PB6") (pin "3") (pinfunction "3_3") (pintype "passive"))
      (node (ref "PB6") (pin "4") (pinfunction "4_4") (pintype "passive"))
      (node (ref "U5") (pin "61") (pinfunction "PD14_61") (pintype "bidirectional"))
    )
    (net (code "6") (name "/B_MODE") (class "Default")
      (node (ref "PB1") (pin "3") (pinfunction "3_3") (pintype "passive"))
      (node (ref "PB1") (pin "4") (pinfunction "4_4") (pintype "passive"))
      (node (ref "U5") (pin "4") (pinfunction "PE5_4") (pintype "bidirectional"))
    )
    (net (code "7") (name "/B_NEXT") (class "Default")
      (node (ref "PB4") (pin "3") (pinfunction "3_3") (pintype "passive"))
      (node (ref "PB4") (pin "4") (pinfunction "4_4") (pintype "passive"))
      (node (ref "U5") (pin "2") (pinfunction "PE3_2") (pintype "bidirectional"))
    )
    (net (code "8") (name "/B_ONOFF") (class "Default")
      (node (ref "PB2") (pin "3") (pinfunction "3_3") (pintype "passive"))
      (node (ref "PB2") (pin "4") (pinfunction "4_4") (pintype "passive"))
      (node (ref "U5") (pin "1") (pinfunction "PE2_1") (pintype "bidirectional"))
    )
    (net (code "9") (name "/B_UP") (class "Default")
      (node (ref "PB5") (pin "3") (pinfunction "3_3") (pintype "passive"))
      (node (ref "PB5") (pin "4") (pinfunction "4_4") (pintype "passive"))
      (node (ref "U5") (pin "62") (pinfunction "PD15_62") (pintype "bidirectional"))
    )
    (net (code "10") (name "/B_VIEW") (class "Default")
      (node (ref "PB3") (pin "3") (pinfunction "3_3") (pintype "passive"))
      (node (ref "PB3") (pin "4") (pinfunction "4_4") (pintype "passive"))
      (node (ref "U5") (pin "3") (pinfunction "PE4_3") (pintype "bidirectional"))
    )
    (net (code "11") (name "/B_ZERO") (class "Default")
      (node (ref "EN1") (pin "S2") (pinfunction "S2_S2") (pintype "passive"))
      (node (ref "U5") (pin "63") (pinfunction "PC6_63") (pintype "bidirectional"))
    )
    (net (code "12") (name "/CAN1_RX") (class "Default")
      (node (ref "TP7") (pin "1") (pinfunction "1_1") (pintype "passive"))
      (node (ref "U5") (pin "81") (pinfunction "PD0_81") (pintype "bidirectional"))
    )
    (net (code "13") (name "/CAN1_TX") (class "Default")
      (node (ref "TP6") (pin "1") (pinfunction "1_1") (pintype "passive"))
      (node (ref "U5") (pin "82") (pinfunction "PD1_82") (pintype "bidirectional"))
    )
    (net (code "14") (name "/CON_RX") (class "Default")
      (node (ref "J1") (pin "2") (pinfunction "2_2") (pintype "bidirectional"))
      (node (ref "R1") (pin "1") (pinfunction "1_1") (pintype "passive"))
    )
    (net (code "15") (name "/CON_TX") (class "Default")
      (node (ref "J1") (pin "3") (pinfunction "3_3") (pintype "bidirectional"))
      (node (ref "R2") (pin "1") (pinfunction "1_1") (pintype "passive"))
    )
    (net (code "16") (name "/ETH_CRS_DV") (class "Default")
      (node (ref "R12") (pin "1") (pinfunction "1_1") (pintype "passive"))
      (node (ref "U5") (pin "32") (pinfunction "PA7_32") (pintype "bidirectional"))
    )
    (net (code "17") (name "/ETH_MDC") (class "Default")
      (node (ref "U4") (pin "13") (pinfunction "MDC_13") (pintype "input"))
      (node (ref "U5") (pin "16") (pinfunction "PC1_16") (pintype "bidirectional"))
    )
    (net (code "18") (name "/ETH_MDIO") (class "Default")
      (node (ref "R16") (pin "1") (pinfunction "1_1") (pintype "passive"))
      (node (ref "U4") (pin "12") (pinfunction "MDIO_12") (pintype "input"))
      (node (ref "U5") (pin "25") (pinfunction "PA2_25") (pintype "bidirectional"))
    )
    (net (code "19") (name "/ETH_REF_CLK") (class "Default")
      (node (ref "R13") (pin "1") (pinfunction "1_1") (pintype "passive"))
      (node (ref "TP2") (pin "1") (pinfunction "1_1") (pintype "passive"))
      (node (ref "U5") (pin "24") (pinfunction "PA1_24") (pintype "bidirectional"))
      (node (ref "U5") (pin "66") (pinfunction "PC9_66") (pintype "bidirectional"))
    )
    (net (code "20") (name "/ETH_RXD0") (class "Default")
      (node (ref "R10") (pin "1") (pinfunction "1_1") (pintype "passive"))
      (node (ref "U5") (pin "33") (pinfunction "PC4_33") (pintype "bidirectional"))
    )
    (net (code "21") (name "/ETH_RXD1") (class "Default")
      (node (ref "R11") (pin "1") (pinfunction "1_1") (pintype "passive"))
      (node (ref "U5") (pin "34") (pinfunction "PC5_34") (pintype "bidirectional"))
    )
    (net (code "22") (name "/ETH_TXD0") (class "Default")
      (node (ref "U4") (pin "17") (pinfunction "TXD0_17") (pintype "input"))
      (node (ref "U5") (pin "51") (pinfunction "PB12_51") (pintype "bidirectional"))
    )
    (net (code "23") (name "/ETH_TXD1") (class "Default")
      (node (ref "U4") (pin "18") (pinfunction "TXD1_18") (pintype "input"))
      (node (ref "U5") (pin "52") (pinfunction "PB13_52") (pintype "bidirectional"))
    )
    (net (code "24") (name "/ETH_TXEN") (class "Default")
      (node (ref "U4") (pin "16") (pinfunction "TXEN_16") (pintype "input"))
      (node (ref "U5") (pin "48") (pinfunction "PB11_48") (pintype "bidirectional"))
    )
    (net (code "25") (name "/GP_ETH_NINT") (class "Default")
      (node (ref "U4") (pin "14") (pinfunction "nINT/REFCLKO_14") (pintype "open_collector"))
      (node (ref "U5") (pin "18") (pinfunction "PC3_18") (pintype "bidirectional"))
    )
    (net (code "26") (name "/GP_ETH_NRST") (class "Default")
      (node (ref "R15") (pin "1") (pinfunction "1_1") (pintype "passive"))
      (node (ref "U4") (pin "15") (pinfunction "nRST_15") (pintype "input"))
      (node (ref "U5") (pin "17") (pinfunction "PC2_17") (pintype "bidirectional"))
    )
    (net (code "27") (name "/GP_GP0") (class "Default")
      (node (ref "J6") (pin "10") (pinfunction "10_10") (pintype "bidirectional"))
      (node (ref "U5") (pin "57") (pinfunction "PD10_57") (pintype "bidirectional"))
    )
    (net (code "28") (name "/GP_GP1") (class "Default")
      (node (ref "J6") (pin "9") (pinfunction "9_9") (pintype "bidirectional"))
      (node (ref "U5") (pin "58") (pinfunction "PD11_58") (pintype "bidirectional"))
    )
    (net (code "29") (name "/I2C1_SCL") (class "Default")
      (node (ref "R6") (pin "1") (pinfunction "1_1") (pintype "passive"))
      (node (ref "U2") (pin "1") (pinfunction "SCL_1") (pintype "input"))
      (node (ref "U5") (pin "95") (pinfunction "PB8_95") (pintype "bidirectional"))
    )
    (net (code "30") (name "/I2C1_SDA") (class "Default")
      (node (ref "R7") (pin "1") (pinfunction "1_1") (pintype "passive"))
      (node (ref "U2") (pin "3") (pinfunction "SDA_3") (pintype "open_collector"))
      (node (ref "U5") (pin "96") (pinfunction "PB9_96") (pintype "bidirectional"))
    )
    (net (code "31") (name "/LCD_CS") (class "Default")
      (node (ref "J6") (pin "6") (pinfunction "6_6") (pintype "bidirectional"))
      (node (ref "U5") (pin "87") (pinfunction "PD6_87") (pintype "bidirectional"))
    )
    (net (code "32") (name "/LCD_DC") (class "Default")
      (node (ref "J6") (pin "5") (pinfunction "5_5") (pintype "bidirectional"))
      (node (ref "U5") (pin "88") (pinfunction "PD7_88") (pintype "bidirectional"))
    )
    (net (code "33") (name "/LCD_LED_PWM") (class "Default")
      (node (ref "J6") (pin "8") (pinfunction "8_8") (pintype "bidirectional"))
      (node (ref "R5") (pin "1") (pinfunction "1_1") (pintype "passive"))
    )
    (net (code "34") (name "/LCD_RST") (class "Default")
      (node (ref "J6") (pin "7") (pinfunction "7_7") (pintype "bidirectional"))
      (node (ref "U5") (pin "86") (pinfunction "PD5_86") (pintype "bidirectional"))
    )
    (net (code "35") (name "/LED_ACT") (class "Default")
      (node (ref "R22") (pin "1") (pinfunction "1_1") (pintype "passive"))
      (node (ref "U4") (pin "3") (pinfunction "LED1/REGOFF_3") (pintype "output"))
    )
    (net (code "36") (name "/LED_GP") (class "Default")
      (node (ref "LD2") (pin "2") (pinfunction "A_2") (pintype "passive"))
      (node (ref "U5") (pin "44") (pinfunction "PE13_44") (pintype "bidirectional"))
    )
    (net (code "37") (name "/LED_SPEED") (class "Default")
      (node (ref "R23") (pin "1") (pinfunction "1_1") (pintype "passive"))
      (node (ref "U4") (pin "2") (pinfunction "LED2/nINTSEL_2") (pintype "output"))
    )
    (net (code "38") (name "/NRST") (class "Default")
      (node (ref "C31") (pin "2") (pinfunction "2_2") (pintype "passive"))
      (node (ref "U5") (pin "14") (pinfunction "NRST_14") (pintype "bidirectional"))
    )
    (net (code "39") (name "/OSC32_IN") (class "Default")
      (node (ref "C10") (pin "2") (pinfunction "2_2") (pintype "passive"))
      (node (ref "U5") (pin "8") (pinfunction "PC14/OSC32_IN_8") (pintype "bidirectional"))
      (node (ref "X1") (pin "2") (pinfunction "OSC2_2") (pintype "passive"))
    )
    (net (code "40") (name "/OSC32_OUT") (class "Default")
      (node (ref "C11") (pin "2") (pinfunction "2_2") (pintype "passive"))
      (node (ref "U5") (pin "9") (pinfunction "PC15/OSC32_OUT_9") (pintype "bidirectional"))
      (node (ref "X1") (pin "1") (pinfunction "OSC1_1") (pintype "passive"))
    )
    (net (code "41") (name "/OSC_IN") (class "Default")
      (node (ref "C13") (pin "2") (pinfunction "2_2") (pintype "passive"))
      (node (ref "U5") (pin "12") (pinfunction "PH0/OSC_IN_12") (pintype "bidirectional"))
      (node (ref "X2") (pin "3") (pinfunction "X_3") (pintype "passive"))
    )
    (net (code "42") (name "/OSC_OUT") (class "Default")
      (node (ref "C14") (pin "2") (pinfunction "2_2") (pintype "passive"))
      (node (ref "U5") (pin "13") (pinfunction "PH1/OSC_OUT_13") (pintype "bidirectional"))
      (node (ref "X2") (pin "1") (pinfunction "X_1") (pintype "passive"))
    )
    (net (code "43") (name "/RCC_MCO1") (class "Default")
      (node (ref "TP1") (pin "1") (pinfunction "1_1") (pintype "passive"))
      (node (ref "U5") (pin "67") (pinfunction "PA8_67") (pintype "bidirectional"))
    )
    (net (code "44") (name "/RD_N") (class "Default")
      (node (ref "R18") (pin "1") (pinfunction "1_1") (pintype "passive"))
      (node (ref "T1") (pin "3") (pinfunction "RD-_3") (pintype "bidirectional"))
      (node (ref "U4") (pin "22") (pinfunction "RXN_22") (pintype "input"))
    )
    (net (code "45") (name "/RD_P") (class "Default")
      (node (ref "R19") (pin "1") (pinfunction "1_1") (pintype "passive"))
      (node (ref "T1") (pin "1") (pinfunction "RD+_1") (pintype "bidirectional"))
      (node (ref "U4") (pin "23") (pinfunction "RXP_23") (pintype "input"))
    )
    (net (code "46") (name "/RX_N") (class "Default")
      (node (ref "J7") (pin "3") (pinfunction "3_3") (pintype "bidirectional"))
      (node (ref "T1") (pin "14") (pinfunction "RX-_14") (pintype "bidirectional"))
    )
    (net (code "47") (name "/RX_P") (class "Default")
      (node (ref "J7") (pin "4") (pinfunction "4_4") (pintype "bidirectional"))
      (node (ref "T1") (pin "16") (pinfunction "RX+_16") (pintype "bidirectional"))
    )
    (net (code "48") (name "/SPI3_CLK") (class "Default")
      (node (ref "J6") (pin "4") (pinfunction "4_4") (pintype "bidirectional"))
      (node (ref "U5") (pin "89") (pinfunction "PB3_89") (pintype "bidirectional"))
    )
    (net (code "49") (name "/SPI3_MISO") (class "Default")
      (node (ref "J6") (pin "3") (pinfunction "3_3") (pintype "bidirectional"))
      (node (ref "U5") (pin "90") (pinfunction "PB4_90") (pintype "bidirectional"))
    )
    (net (code "50") (name "/SPI3_MOSI") (class "Default")
      (node (ref "J6") (pin "2") (pinfunction "2_2") (pintype "bidirectional"))
      (node (ref "U5") (pin "91") (pinfunction "PB5_91") (pintype "bidirectional"))
    )
    (net (code "51") (name "/SWCLK") (class "Default")
      (node (ref "J3") (pin "2") (pinfunction "2_2") (pintype "bidirectional"))
      (node (ref "U5") (pin "76") (pinfunction "PA14_76") (pintype "bidirectional"))
    )
    (net (code "52") (name "/SWDIO") (class "Default")
      (node (ref "J3") (pin "4") (pinfunction "4_4") (pintype "bidirectional"))
      (node (ref "U5") (pin "72") (pinfunction "PA13_72") (pintype "bidirectional"))
    )
    (net (code "53") (name "/TD_N") (class "Default")
      (node (ref "R20") (pin "1") (pinfunction "1_1") (pintype "passive"))
      (node (ref "T1") (pin "8") (pinfunction "TD-_8") (pintype "bidirectional"))
      (node (ref "U4") (pin "20") (pinfunction "TXN_20") (pintype "output"))
    )
    (net (code "54") (name "/TD_P") (class "Default")
      (node (ref "R21") (pin "1") (pinfunction "1_1") (pintype "passive"))
      (node (ref "T1") (pin "6") (pinfunction "TD+_6") (pintype "bidirectional"))
      (node (ref "U4") (pin "21") (pinfunction "TXP_21") (pintype "output"))
    )
    (net (code "55") (name "/TIM4_CH1") (class "Default")
      (node (ref "C5") (pin "2") (pinfunction "2_2") (pintype "passive"))
      (node (ref "EN1") (pin "A") (pinfunction "A_A") (pintype "passive"))
      (node (ref "U5") (pin "59") (pinfunction "PD12_59") (pintype "bidirectional"))
    )
    (net (code "56") (name "/TIM4_CH2") (class "Default")
      (node (ref "C6") (pin "2") (pinfunction "2_2") (pintype "passive"))
      (node (ref "EN1") (pin "B") (pinfunction "B_B") (pintype "passive"))
      (node (ref "U5") (pin "60") (pinfunction "PD13_60") (pintype "bidirectional"))
    )
    (net (code "57") (name "/TIM8_CH2") (class "Default")
      (node (ref "R5") (pin "2") (pinfunction "2_2") (pintype "passive"))
      (node (ref "U5") (pin "64") (pinfunction "PC7_64") (pintype "bidirectional"))
    )
    (net (code "58") (name "/TIM12_CH1") (class "Default")
      (node (ref "R8") (pin "2") (pinfunction "2_2") (pintype "passive"))
      (node (ref "U5") (pin "53") (pinfunction "PB14_53") (pintype "bidirectional"))
    )
    (net (code "59") (name "/TIM12_CH2") (class "Default")
      (node (ref "LS1") (pin "1") (pinfunction "OSC1_1") (pintype "passive"))
      (node (ref "U5") (pin "54") (pinfunction "PB15_54") (pintype "bidirectional"))
    )
    (net (code "60") (name "/TX_N") (class "Default")
      (node (ref "J7") (pin "1") (pinfunction "1_1") (pintype "bidirectional"))
      (node (ref "T1") (pin "9") (pinfunction "TX-_9") (pintype "bidirectional"))
    )
    (net (code "61") (name "/TX_P") (class "Default")
      (node (ref "J7") (pin "2") (pinfunction "2_2") (pintype "bidirectional"))
      (node (ref "T1") (pin "11") (pinfunction "TX+_11") (pintype "bidirectional"))
    )
    (net (code "62") (name "/UART1_RX") (class "Default")
      (node (ref "R1") (pin "2") (pinfunction "2_2") (pintype "passive"))
      (node (ref "U1") (pin "6") (pinfunction "I/O4_6") (pintype "bidirectional"))
      (node (ref "U5") (pin "93") (pinfunction "PB7_93") (pintype "bidirectional"))
    )
    (net (code "63") (name "/UART1_TX") (class "Default")
      (node (ref "R2") (pin "2") (pinfunction "2_2") (pintype "passive"))
      (node (ref "U1") (pin "4") (pinfunction "I/O3_4") (pintype "bidirectional"))
      (node (ref "U5") (pin "92") (pinfunction "PB6_92") (pintype "bidirectional"))
    )
    (net (code "64") (name "/UART3_RX") (class "Default")
      (node (ref "J6") (pin "11") (pinfunction "11_11") (pintype "bidirectional"))
      (node (ref "U5") (pin "56") (pinfunction "PD9_56") (pintype "bidirectional"))
    )
    (net (code "65") (name "/UART3_TX") (class "Default")
      (node (ref "J6") (pin "12") (pinfunction "12_12") (pintype "bidirectional"))
      (node (ref "U5") (pin "55") (pinfunction "PD8_55") (pintype "bidirectional"))
    )
    (net (code "66") (name "/UART4_RX") (class "Default")
      (node (ref "J2") (pin "4") (pinfunction "4_4") (pintype "bidirectional"))
      (node (ref "U5") (pin "79") (pinfunction "PC11_79") (pintype "bidirectional"))
    )
    (net (code "67") (name "/UART4_TX") (class "Default")
      (node (ref "J2") (pin "2") (pinfunction "2_2") (pintype "bidirectional"))
      (node (ref "U5") (pin "78") (pinfunction "PC10_78") (pintype "bidirectional"))
    )
    (net (code "68") (name "/USB_OTG_FS_DM") (class "Default")
      (node (ref "TP4") (pin "1") (pinfunction "1_1") (pintype "passive"))
      (node (ref "U5") (pin "70") (pinfunction "PA11_70") (pintype "bidirectional"))
    )
    (net (code "69") (name "/USB_OTG_FS_DP") (class "Default")
      (node (ref "TP3") (pin "1") (pinfunction "1_1") (pintype "passive"))
      (node (ref "U5") (pin "71") (pinfunction "PA12_71") (pintype "bidirectional"))
    )
    (net (code "70") (name "/USB_OTG_FS_ID") (class "Default")
      (node (ref "TP5") (pin "1") (pinfunction "1_1") (pintype "passive"))
      (node (ref "U5") (pin "69") (pinfunction "PA10_69") (pintype "bidirectional"))
    )
    (net (code "71") (name "/USB_OTG_FS_VBUS") (class "Default")
      (node (ref "U5") (pin "68") (pinfunction "PA9_68") (pintype "bidirectional"))
    )
    (net (code "72") (name "/VBAT") (class "Default")
      (node (ref "C1") (pin "2") (pinfunction "2_2") (pintype "passive"))
      (node (ref "SK1") (pin "1") (pinfunction "1_1") (pintype "bidirectional"))
      (node (ref "U5") (pin "6") (pinfunction "VBAT_6") (pintype "power_in"))
    )
    (net (code "73") (name "/VCAP1") (class "Default")
      (node (ref "C29") (pin "2") (pinfunction "2_2") (pintype "passive"))
      (node (ref "U5") (pin "49") (pinfunction "VCAP_1_49") (pintype "power_in"))
    )
    (net (code "74") (name "/VCAP2") (class "Default")
      (node (ref "C30") (pin "2") (pinfunction "2_2") (pintype "passive"))
      (node (ref "U5") (pin "73") (pinfunction "VCAP_2_73") (pintype "power_in"))
    )
    (net (code "75") (name "/VDD_LAN") (class "Default")
      (node (ref "C12") (pin "1") (pinfunction "1_1") (pintype "passive"))
      (node (ref "C15") (pin "2") (pinfunction "2_2") (pintype "passive"))
      (node (ref "C16") (pin "2") (pinfunction "2_2") (pintype "passive"))
      (node (ref "C17") (pin "2") (pinfunction "2_2") (pintype "passive"))
      (node (ref "C18") (pin "1") (pinfunction "1_1") (pintype "passive"))
      (node (ref "C19") (pin "1") (pinfunction "1_1") (pintype "passive"))
      (node (ref "L1") (pin "1") (pinfunction "1_1") (pintype "passive"))
      (node (ref "LD3") (pin "2") (pinfunction "A_2") (pintype "passive"))
      (node (ref "R18") (pin "2") (pinfunction "2_2") (pintype "passive"))
      (node (ref "R19") (pin "2") (pinfunction "2_2") (pintype "passive"))
      (node (ref "R20") (pin "2") (pinfunction "2_2") (pintype "passive"))
      (node (ref "R21") (pin "2") (pinfunction "2_2") (pintype "passive"))
      (node (ref "T1") (pin "2") (pinfunction "RDCT_2") (pintype "bidirectional"))
      (node (ref "T1") (pin "7") (pinfunction "TDCT_7") (pintype "bidirectional"))
      (node (ref "U4") (pin "1") (pinfunction "VDD2A_1") (pintype "power_in"))
      (node (ref "U4") (pin "19") (pinfunction "VDD1A_19") (pintype "power_in"))
    )
    (net (code "76") (name "Net-(D1-C)") (class "Default")
      (node (ref "C4") (pin "2") (pinfunction "2_2") (pintype "passive"))
      (node (ref "D1") (pin "1") (pinfunction "C_1") (pintype "passive"))
      (node (ref "U3") (pin "3") (pinfunction "IN_3") (pintype "power_in"))
    )
    (net (code "77") (name "Net-(EN1-PadC)") (class "Default")
      (node (ref "EN1") (pin "C") (pinfunction "C_C") (pintype "passive"))
      (node (ref "R4") (pin "2") (pinfunction "2_2") (pintype "passive"))
    )
    (net (code "78") (name "Net-(LD1-C)") (class "Default")
      (node (ref "LD1") (pin "1") (pinfunction "C_1") (pintype "passive"))
      (node (ref "R9") (pin "1") (pinfunction "1_1") (pintype "passive"))
    )
    (net (code "79") (name "Net-(LD2-C)") (class "Default")
      (node (ref "LD2") (pin "1") (pinfunction "C_1") (pintype "passive"))
      (node (ref "R14") (pin "1") (pinfunction "1_1") (pintype "passive"))
    )
    (net (code "80") (name "Net-(LD3-C)") (class "Default")
      (node (ref "LD3") (pin "1") (pinfunction "C_1") (pintype "passive"))
      (node (ref "R23") (pin "2") (pinfunction "2_2") (pintype "passive"))
    )
    (net (code "81") (name "Net-(LD4-A)") (class "Default")
      (node (ref "LD4") (pin "2") (pinfunction "A_2") (pintype "passive"))
      (node (ref "R22") (pin "2") (pinfunction "2_2") (pintype "passive"))
    )
    (net (code "82") (name "Net-(LS1-OSC2)") (class "Default")
      (node (ref "LS1") (pin "2") (pinfunction "OSC2_2") (pintype "passive"))
      (node (ref "R8") (pin "1") (pinfunction "1_1") (pintype "passive"))
    )
    (net (code "83") (name "Net-(U4-CRS_DV{slash}MODE2)") (class "Default")
      (node (ref "R12") (pin "2") (pinfunction "2_2") (pintype "passive"))
      (node (ref "U4") (pin "11") (pinfunction "CRS_DV/MODE2_11") (pintype "output"))
    )
    (net (code "84") (name "Net-(U4-RBIAS)") (class "Default")
      (node (ref "R17") (pin "1") (pinfunction "1_1") (pintype "passive"))
      (node (ref "U4") (pin "24") (pinfunction "RBIAS_24") (pintype "input"))
    )
    (net (code "85") (name "Net-(U4-RXD0{slash}MODE0)") (class "Default")
      (node (ref "R10") (pin "2") (pinfunction "2_2") (pintype "passive"))
      (node (ref "U4") (pin "8") (pinfunction "RXD0/MODE0_8") (pintype "output"))
    )
    (net (code "86") (name "Net-(U4-RXD1{slash}MODE1)") (class "Default")
      (node (ref "R11") (pin "2") (pinfunction "2_2") (pintype "passive"))
      (node (ref "U4") (pin "7") (pinfunction "RXD1/MODE1_7") (pintype "output"))
    )
    (net (code "87") (name "Net-(U4-VDDCR)") (class "Default")
      (node (ref "C8") (pin "2") (pinfunction "2_2") (pintype "passive"))
      (node (ref "C9") (pin "2") (pinfunction "2_2") (pintype "passive"))
      (node (ref "U4") (pin "6") (pinfunction "VDDCR_6") (pintype "power_in"))
    )
    (net (code "88") (name "Net-(U4-XTAL1{slash}CLKIN)") (class "Default")
      (node (ref "R13") (pin "2") (pinfunction "2_2") (pintype "passive"))
      (node (ref "U4") (pin "5") (pinfunction "XTAL1/CLKIN_5") (pintype "input"))
    )
    (net (code "89") (name "unconnected-(J5-Pad1)") (class "Default")
      (node (ref "J5") (pin "1") (pinfunction "1_1") (pintype "bidirectional"))
    )
    (net (code "90") (name "unconnected-(J5-Pad2)") (class "Default")
      (node (ref "J5") (pin "2") (pinfunction "2_2") (pintype "bidirectional"))
    )
    (net (code "91") (name "unconnected-(J5-Pad3)") (class "Default")
      (node (ref "J5") (pin "3") (pinfunction "3_3") (pintype "bidirectional"))
    )
    (net (code "92") (name "unconnected-(J5-Pad4)") (class "Default")
      (node (ref "J5") (pin "4") (pinfunction "4_4") (pintype "bidirectional"))
    )
    (net (code "93") (name "unconnected-(J5-Pad5)") (class "Default")
      (node (ref "J5") (pin "5") (pinfunction "5_5") (pintype "bidirectional"))
    )
    (net (code "94") (name "unconnected-(J5-Pad6)") (class "Default")
      (node (ref "J5") (pin "6") (pinfunction "6_6") (pintype "bidirectional"))
    )
    (net (code "95") (name "unconnected-(J5-Pad7)") (class "Default")
      (node (ref "J5") (pin "7") (pinfunction "7_7") (pintype "bidirectional"))
    )
    (net (code "96") (name "unconnected-(J5-Pad8)") (class "Default")
      (node (ref "J5") (pin "8") (pinfunction "8_8") (pintype "bidirectional"))
    )
    (net (code "97") (name "unconnected-(J5-Pad11)") (class "Default")
      (node (ref "J5") (pin "11") (pinfunction "11_11") (pintype "bidirectional"))
    )
    (net (code "98") (name "unconnected-(J5-Pad12)") (class "Default")
      (node (ref "J5") (pin "12") (pinfunction "12_12") (pintype "bidirectional"))
    )
    (net (code "99") (name "unconnected-(J5-Pad13)") (class "Default")
      (node (ref "J5") (pin "13") (pinfunction "13_13") (pintype "bidirectional"))
    )
    (net (code "100") (name "unconnected-(J5-Pad14)") (class "Default")
      (node (ref "J5") (pin "14") (pinfunction "14_14") (pintype "bidirectional"))
    )
    (net (code "101") (name "unconnected-(T1-NC-Pad4)") (class "Default")
      (node (ref "T1") (pin "4") (pinfunction "NC_4") (pintype "passive"))
    )
    (net (code "102") (name "unconnected-(T1-NC-Pad5)") (class "Default")
      (node (ref "T1") (pin "5") (pinfunction "NC_5") (pintype "passive"))
    )
    (net (code "103") (name "unconnected-(T1-NC-Pad12)") (class "Default")
      (node (ref "T1") (pin "12") (pinfunction "NC_12") (pintype "passive"))
    )
    (net (code "104") (name "unconnected-(T1-NC-Pad13)") (class "Default")
      (node (ref "T1") (pin "13") (pinfunction "NC_13") (pintype "passive"))
    )
    (net (code "105") (name "unconnected-(T1-RXCT-Pad15)") (class "Default")
      (node (ref "T1") (pin "15") (pinfunction "RXCT_15") (pintype "bidirectional"))
    )
    (net (code "106") (name "unconnected-(T1-TXCT-Pad10)") (class "Default")
      (node (ref "T1") (pin "10") (pinfunction "TXCT_10") (pintype "bidirectional"))
    )
    (net (code "107") (name "unconnected-(U1-I{slash}O1-Pad1)") (class "Default")
      (node (ref "U1") (pin "1") (pinfunction "I/O1_1") (pintype "bidirectional"))
    )
    (net (code "108") (name "unconnected-(U1-I{slash}O2-Pad3)") (class "Default")
      (node (ref "U1") (pin "3") (pinfunction "I/O2_3") (pintype "bidirectional"))
    )
    (net (code "109") (name "unconnected-(U1-VP-Pad5)") (class "Default")
      (node (ref "U1") (pin "5") (pinfunction "VP_5") (pintype "power_in"))
    )
    (net (code "110") (name "unconnected-(U4-RXER{slash}PHYAD0-Pad10)") (class "Default")
      (node (ref "U4") (pin "10") (pinfunction "RXER/PHYAD0_10") (pintype "output"))
    )
    (net (code "111") (name "unconnected-(U4-XTAL2-Pad4)") (class "Default")
      (node (ref "U4") (pin "4") (pinfunction "XTAL2_4") (pintype "output"))
    )
    (net (code "112") (name "unconnected-(U5-PA0{slash}WKUP-Pad23)") (class "Default")
      (node (ref "U5") (pin "23") (pinfunction "PA0/WKUP_23") (pintype "bidirectional"))
    )
    (net (code "113") (name "unconnected-(U5-PA3-Pad26)") (class "Default")
      (node (ref "U5") (pin "26") (pinfunction "PA3_26") (pintype "bidirectional"))
    )
    (net (code "114") (name "unconnected-(U5-PA4-Pad29)") (class "Default")
      (node (ref "U5") (pin "29") (pinfunction "PA4_29") (pintype "bidirectional"))
    )
    (net (code "115") (name "unconnected-(U5-PA5-Pad30)") (class "Default")
      (node (ref "U5") (pin "30") (pinfunction "PA5_30") (pintype "bidirectional"))
    )
    (net (code "116") (name "unconnected-(U5-PA6-Pad31)") (class "Default")
      (node (ref "U5") (pin "31") (pinfunction "PA6_31") (pintype "bidirectional"))
    )
    (net (code "117") (name "unconnected-(U5-PA15-Pad77)") (class "Default")
      (node (ref "U5") (pin "77") (pinfunction "PA15_77") (pintype "bidirectional"))
    )
    (net (code "118") (name "unconnected-(U5-PB0-Pad35)") (class "Default")
      (node (ref "U5") (pin "35") (pinfunction "PB0_35") (pintype "bidirectional"))
    )
    (net (code "119") (name "unconnected-(U5-PB1-Pad36)") (class "Default")
      (node (ref "U5") (pin "36") (pinfunction "PB1_36") (pintype "bidirectional"))
    )
    (net (code "120") (name "unconnected-(U5-PB10-Pad47)") (class "Default")
      (node (ref "U5") (pin "47") (pinfunction "PB10_47") (pintype "bidirectional"))
    )
    (net (code "121") (name "unconnected-(U5-PC0-Pad15)") (class "Default")
      (node (ref "U5") (pin "15") (pinfunction "PC0_15") (pintype "bidirectional"))
    )
    (net (code "122") (name "unconnected-(U5-PC8-Pad65)") (class "Default")
      (node (ref "U5") (pin "65") (pinfunction "PC8_65") (pintype "bidirectional"))
    )
    (net (code "123") (name "unconnected-(U5-PC12-Pad80)") (class "Default")
      (node (ref "U5") (pin "80") (pinfunction "PC12_80") (pintype "bidirectional"))
    )
    (net (code "124") (name "unconnected-(U5-PC13-Pad7)") (class "Default")
      (node (ref "U5") (pin "7") (pinfunction "PC13_7") (pintype "bidirectional"))
    )
    (net (code "125") (name "unconnected-(U5-PD2-Pad83)") (class "Default")
      (node (ref "U5") (pin "83") (pinfunction "PD2_83") (pintype "bidirectional"))
    )
    (net (code "126") (name "unconnected-(U5-PD3-Pad84)") (class "Default")
      (node (ref "U5") (pin "84") (pinfunction "PD3_84") (pintype "bidirectional"))
    )
    (net (code "127") (name "unconnected-(U5-PD4-Pad85)") (class "Default")
      (node (ref "U5") (pin "85") (pinfunction "PD4_85") (pintype "bidirectional"))
    )
    (net (code "128") (name "unconnected-(U5-PE0-Pad97)") (class "Default")
      (node (ref "U5") (pin "97") (pinfunction "PE0_97") (pintype "bidirectional"))
    )
    (net (code "129") (name "unconnected-(U5-PE1-Pad98)") (class "Default")
      (node (ref "U5") (pin "98") (pinfunction "PE1_98") (pintype "bidirectional"))
    )
    (net (code "130") (name "unconnected-(U5-PE6-Pad5)") (class "Default")
      (node (ref "U5") (pin "5") (pinfunction "PE6_5") (pintype "bidirectional"))
    )
    (net (code "131") (name "unconnected-(U5-PE7-Pad38)") (class "Default")
      (node (ref "U5") (pin "38") (pinfunction "PE7_38") (pintype "bidirectional"))
    )
    (net (code "132") (name "unconnected-(U5-PE8-Pad39)") (class "Default")
      (node (ref "U5") (pin "39") (pinfunction "PE8_39") (pintype "bidirectional"))
    )
    (net (code "133") (name "unconnected-(U5-PE9-Pad40)") (class "Default")
      (node (ref "U5") (pin "40") (pinfunction "PE9_40") (pintype "bidirectional"))
    )
    (net (code "134") (name "unconnected-(U5-PE10-Pad41)") (class "Default")
      (node (ref "U5") (pin "41") (pinfunction "PE10_41") (pintype "bidirectional"))
    )
    (net (code "135") (name "unconnected-(U5-PE11-Pad42)") (class "Default")
      (node (ref "U5") (pin "42") (pinfunction "PE11_42") (pintype "bidirectional"))
    )
    (net (code "136") (name "unconnected-(U5-PE12-Pad43)") (class "Default")
      (node (ref "U5") (pin "43") (pinfunction "PE12_43") (pintype "bidirectional"))
    )
    (net (code "137") (name "unconnected-(U5-PE14-Pad45)") (class "Default")
      (node (ref "U5") (pin "45") (pinfunction "PE14_45") (pintype "bidirectional"))
    )
    (net (code "138") (name "unconnected-(U5-PE15-Pad46)") (class "Default")
      (node (ref "U5") (pin "46") (pinfunction "PE15_46") (pintype "bidirectional"))
    )
  )
)
